# ltk-hall_main_vh.net
KiCad netlist of a schematic drawn in Altium Designer
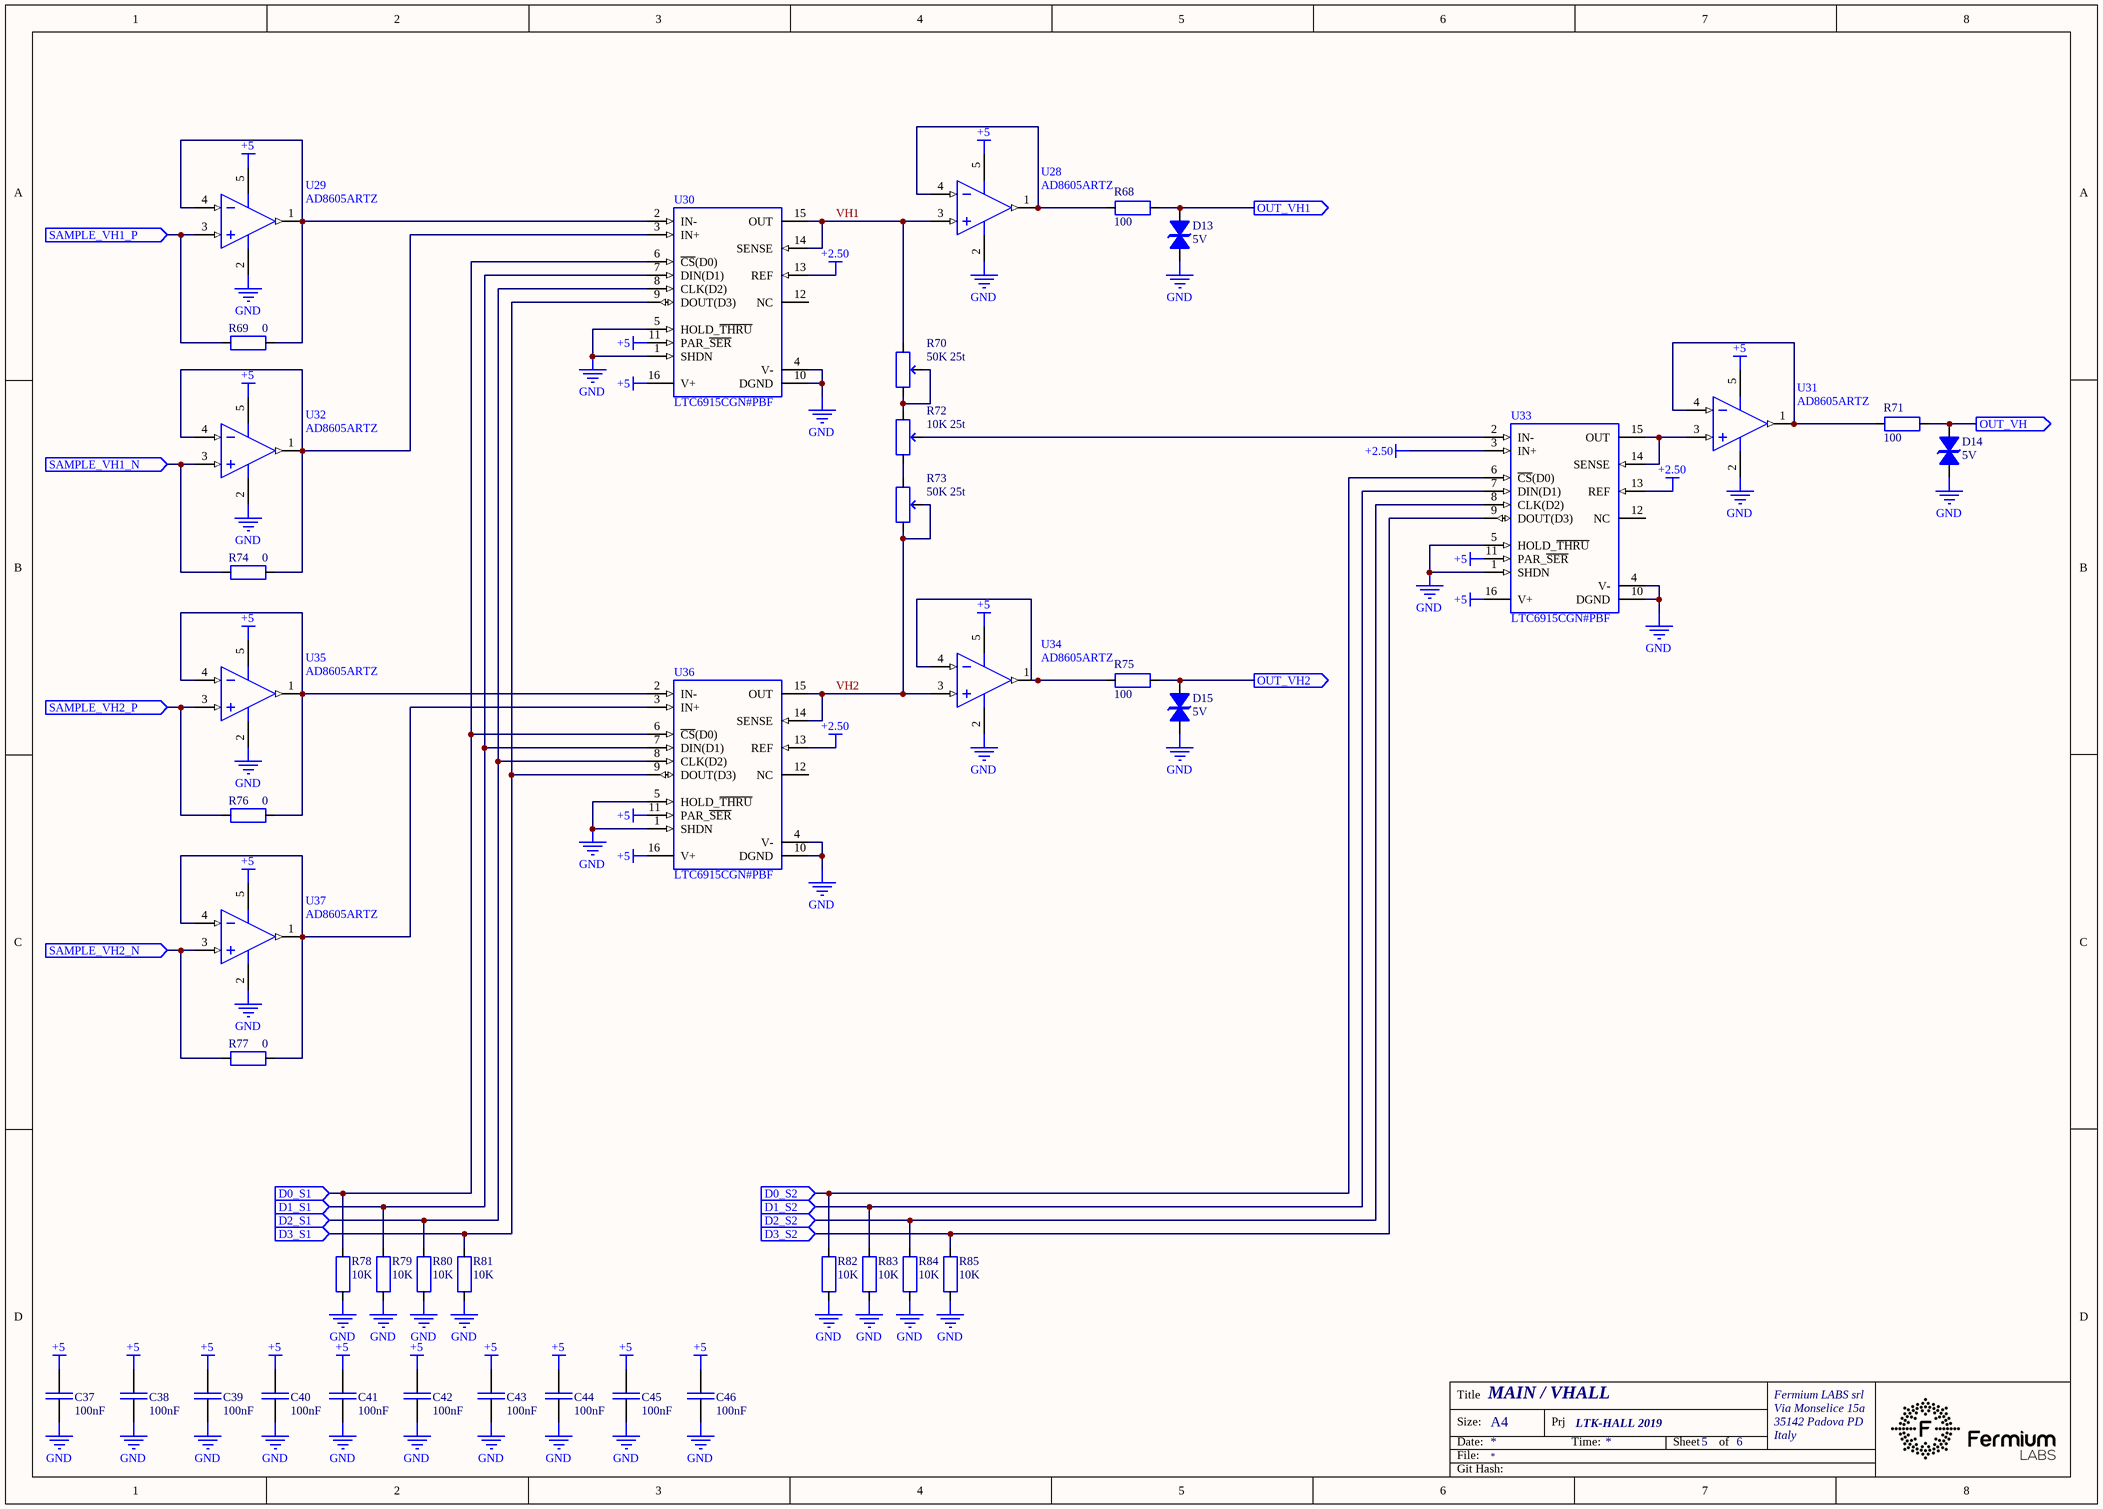
[diagram p0: ltk-hall_main_vh.SchDoc]

(export (version "E")
  (design (tool "Eeschema 10.0.6"))
  (components
    (comp (ref "C37")
      (value "100nF")
      (footprint "CAP 0603_1608")
      (description "CAP SMD MLCC 100nF 25V 0603 X7R")
      (fields (field (name "PART NUMBER") "02841f84-ac15-41b5-9e17-915f8f067828"))
      (libsource (lib "frmdblib") (part "GENERIC_C"))
    )
    (comp (ref "C38")
      (value "100nF")
      (footprint "CAP 0603_1608")
      (description "CAP SMD MLCC 100nF 25V 0603 X7R")
      (fields (field (name "PART NUMBER") "02841f84-ac15-41b5-9e17-915f8f067828"))
      (libsource (lib "frmdblib") (part "GENERIC_C"))
    )
    (comp (ref "C39")
      (value "100nF")
      (footprint "CAP 0603_1608")
      (description "CAP SMD MLCC 100nF 25V 0603 X7R")
      (fields (field (name "PART NUMBER") "02841f84-ac15-41b5-9e17-915f8f067828"))
      (libsource (lib "frmdblib") (part "GENERIC_C"))
    )
    (comp (ref "C40")
      (value "100nF")
      (footprint "CAP 0603_1608")
      (description "CAP SMD MLCC 100nF 25V 0603 X7R")
      (fields (field (name "PART NUMBER") "02841f84-ac15-41b5-9e17-915f8f067828"))
      (libsource (lib "frmdblib") (part "GENERIC_C"))
    )
    (comp (ref "C41")
      (value "100nF")
      (footprint "CAP 0603_1608")
      (description "CAP SMD MLCC 100nF 25V 0603 X7R")
      (fields (field (name "PART NUMBER") "02841f84-ac15-41b5-9e17-915f8f067828"))
      (libsource (lib "frmdblib") (part "GENERIC_C"))
    )
    (comp (ref "C42")
      (value "100nF")
      (footprint "CAP 0603_1608")
      (description "CAP SMD MLCC 100nF 25V 0603 X7R")
      (fields (field (name "PART NUMBER") "02841f84-ac15-41b5-9e17-915f8f067828"))
      (libsource (lib "frmdblib") (part "GENERIC_C"))
    )
    (comp (ref "C43")
      (value "100nF")
      (footprint "CAP 0603_1608")
      (description "CAP SMD MLCC 100nF 25V 0603 X7R")
      (fields (field (name "PART NUMBER") "02841f84-ac15-41b5-9e17-915f8f067828"))
      (libsource (lib "frmdblib") (part "GENERIC_C"))
    )
    (comp (ref "C44")
      (value "100nF")
      (footprint "CAP 0603_1608")
      (description "CAP SMD MLCC 100nF 25V 0603 X7R")
      (fields (field (name "PART NUMBER") "02841f84-ac15-41b5-9e17-915f8f067828"))
      (libsource (lib "frmdblib") (part "GENERIC_C"))
    )
    (comp (ref "C45")
      (value "100nF")
      (footprint "CAP 0603_1608")
      (description "CAP SMD MLCC 100nF 25V 0603 X7R")
      (fields (field (name "PART NUMBER") "02841f84-ac15-41b5-9e17-915f8f067828"))
      (libsource (lib "frmdblib") (part "GENERIC_C"))
    )
    (comp (ref "C46")
      (value "100nF")
      (footprint "CAP 0603_1608")
      (description "CAP SMD MLCC 100nF 25V 0603 X7R")
      (fields (field (name "PART NUMBER") "02841f84-ac15-41b5-9e17-915f8f067828"))
      (libsource (lib "frmdblib") (part "GENERIC_C"))
    )
    (comp (ref "D13")
      (value "5V")
      (footprint "SOD523F")
      (description "DIODE SMD TVS 5V BIDIRECTIONAL SOD-523")
      (fields (field (name "PART NUMBER") "daa58212-38e2-4326-a156-8e48058c46f1"))
      (libsource (lib "frmdblib") (part "GENERIC_D_TVS_BI"))
    )
    (comp (ref "D14")
      (value "5V")
      (footprint "SOD523F")
      (description "DIODE SMD TVS 5V BIDIRECTIONAL SOD-523")
      (fields (field (name "PART NUMBER") "daa58212-38e2-4326-a156-8e48058c46f1"))
      (libsource (lib "frmdblib") (part "GENERIC_D_TVS_BI"))
    )
    (comp (ref "D15")
      (value "5V")
      (footprint "SOD523F")
      (description "DIODE SMD TVS 5V BIDIRECTIONAL SOD-523")
      (fields (field (name "PART NUMBER") "daa58212-38e2-4326-a156-8e48058c46f1"))
      (libsource (lib "frmdblib") (part "GENERIC_D_TVS_BI"))
    )
    (comp (ref "R68")
      (value "100")
      (footprint "RES 0603_1608")
      (description "RES SMD 100 OHM 1% 1/10W 0603")
      (fields (field (name "PART NUMBER") "0a6c4b74-f837-4563-b154-6e196d753525"))
      (libsource (lib "frmdblib") (part "GENERIC_R"))
    )
    (comp (ref "R69")
      (value "0")
      (footprint "RES 0603_1608")
      (description "RES SMD 0 OHM 5% 1/10W 0603")
      (fields (field (name "PART NUMBER") "6ae227f9-847f-4766-8522-e11a83531204"))
      (libsource (lib "frmdblib") (part "GENERIC_R"))
    )
    (comp (ref "R70")
      (value "50K 25t")
      (footprint "F9540903-09ED-4909-856A-DED10E64451E")
      (description "POT TRIMMER LINEAR 50K 25TURNS VERT THT")
      (fields (field (name "PART NUMBER") "90164141-8820-4471-9a6f-9a984ce9068c"))
      (libsource (lib "frmdblib") (part "GENERIC_R_VAR"))
    )
    (comp (ref "R71")
      (value "100")
      (footprint "RES 0603_1608")
      (description "RES SMD 100 OHM 1% 1/10W 0603")
      (fields (field (name "PART NUMBER") "0a6c4b74-f837-4563-b154-6e196d753525"))
      (libsource (lib "frmdblib") (part "GENERIC_R"))
    )
    (comp (ref "R72")
      (value "10K 25t")
      (footprint "F9540903-09ED-4909-856A-DED10E64451E")
      (description "POT TRIMMER LINEAR 10K 25TURNS VERT THT")
      (fields (field (name "PART NUMBER") "613f65ed-4d8d-44d0-9fe5-67eff78392c9"))
      (libsource (lib "frmdblib") (part "GENERIC_R_VAR"))
    )
    (comp (ref "R73")
      (value "50K 25t")
      (footprint "F9540903-09ED-4909-856A-DED10E64451E")
      (description "POT TRIMMER LINEAR 50K 25TURNS VERT THT")
      (fields (field (name "PART NUMBER") "90164141-8820-4471-9a6f-9a984ce9068c"))
      (libsource (lib "frmdblib") (part "GENERIC_R_VAR"))
    )
    (comp (ref "R74")
      (value "0")
      (footprint "RES 0603_1608")
      (description "RES SMD 0 OHM 5% 1/10W 0603")
      (fields (field (name "PART NUMBER") "6ae227f9-847f-4766-8522-e11a83531204"))
      (libsource (lib "frmdblib") (part "GENERIC_R"))
    )
    (comp (ref "R75")
      (value "100")
      (footprint "RES 0603_1608")
      (description "RES SMD 100 OHM 1% 1/10W 0603")
      (fields (field (name "PART NUMBER") "0a6c4b74-f837-4563-b154-6e196d753525"))
      (libsource (lib "frmdblib") (part "GENERIC_R"))
    )
    (comp (ref "R76")
      (value "0")
      (footprint "RES 0603_1608")
      (description "RES SMD 0 OHM 5% 1/10W 0603")
      (fields (field (name "PART NUMBER") "6ae227f9-847f-4766-8522-e11a83531204"))
      (libsource (lib "frmdblib") (part "GENERIC_R"))
    )
    (comp (ref "R77")
      (value "0")
      (footprint "RES 0603_1608")
      (description "RES SMD 0 OHM 5% 1/10W 0603")
      (fields (field (name "PART NUMBER") "6ae227f9-847f-4766-8522-e11a83531204"))
      (libsource (lib "frmdblib") (part "GENERIC_R"))
    )
    (comp (ref "R78")
      (value "10K")
      (footprint "RES 0603_1608")
      (description "RES SMD 10K OHM 1% 1/10W 0603")
      (fields (field (name "PART NUMBER") "93242766-ba1d-462d-b58f-ce1dfc4129c8"))
      (libsource (lib "frmdblib") (part "GENERIC_R"))
    )
    (comp (ref "R79")
      (value "10K")
      (footprint "RES 0603_1608")
      (description "RES SMD 10K OHM 1% 1/10W 0603")
      (fields (field (name "PART NUMBER") "93242766-ba1d-462d-b58f-ce1dfc4129c8"))
      (libsource (lib "frmdblib") (part "GENERIC_R"))
    )
    (comp (ref "R80")
      (value "10K")
      (footprint "RES 0603_1608")
      (description "RES SMD 10K OHM 1% 1/10W 0603")
      (fields (field (name "PART NUMBER") "93242766-ba1d-462d-b58f-ce1dfc4129c8"))
      (libsource (lib "frmdblib") (part "GENERIC_R"))
    )
    (comp (ref "R81")
      (value "10K")
      (footprint "RES 0603_1608")
      (description "RES SMD 10K OHM 1% 1/10W 0603")
      (fields (field (name "PART NUMBER") "93242766-ba1d-462d-b58f-ce1dfc4129c8"))
      (libsource (lib "frmdblib") (part "GENERIC_R"))
    )
    (comp (ref "R82")
      (value "10K")
      (footprint "RES 0603_1608")
      (description "RES SMD 10K OHM 1% 1/10W 0603")
      (fields (field (name "PART NUMBER") "93242766-ba1d-462d-b58f-ce1dfc4129c8"))
      (libsource (lib "frmdblib") (part "GENERIC_R"))
    )
    (comp (ref "R83")
      (value "10K")
      (footprint "RES 0603_1608")
      (description "RES SMD 10K OHM 1% 1/10W 0603")
      (fields (field (name "PART NUMBER") "93242766-ba1d-462d-b58f-ce1dfc4129c8"))
      (libsource (lib "frmdblib") (part "GENERIC_R"))
    )
    (comp (ref "R84")
      (value "10K")
      (footprint "RES 0603_1608")
      (description "RES SMD 10K OHM 1% 1/10W 0603")
      (fields (field (name "PART NUMBER") "93242766-ba1d-462d-b58f-ce1dfc4129c8"))
      (libsource (lib "frmdblib") (part "GENERIC_R"))
    )
    (comp (ref "R85")
      (value "10K")
      (footprint "RES 0603_1608")
      (description "RES SMD 10K OHM 1% 1/10W 0603")
      (fields (field (name "PART NUMBER") "93242766-ba1d-462d-b58f-ce1dfc4129c8"))
      (libsource (lib "frmdblib") (part "GENERIC_R"))
    )
    (comp (ref "U28")
      (value "AD8605ARTZ")
      (footprint "A3DDA0BC-073E-4B18-9613-F713A7EC1E27")
      (description "IC OPAMP 65uV 1pA RRIO 5V 80mA SOT-23-5")
      (fields (field (name "PART NUMBER") "5610e9ea-bca8-49b2-8e5f-11409231f6a4"))
      (libsource (lib "frmdblib") (part "8096D751-9DCE-401B-B65E-AAEE0733EA70"))
    )
    (comp (ref "U29")
      (value "AD8605ARTZ")
      (footprint "A3DDA0BC-073E-4B18-9613-F713A7EC1E27")
      (description "IC OPAMP 65uV 1pA RRIO 5V 80mA SOT-23-5")
      (fields (field (name "PART NUMBER") "5610e9ea-bca8-49b2-8e5f-11409231f6a4"))
      (libsource (lib "frmdblib") (part "8096D751-9DCE-401B-B65E-AAEE0733EA70"))
    )
    (comp (ref "U30")
      (value "LTC6915CGN#PBF")
      (footprint "517EE8A2-9FD8-4174-996D-BDBF76CA3EEB")
      (description "IC PGA G0-4094 SPI-PARALLEL 5V RRIO SSOP-16")
      (fields (field (name "PART NUMBER") "59fe82cd-fd18-4813-9f52-e2e78a460aff"))
      (libsource (lib "frmdblib") (part "092C41BF-C4B2-4D13-B4E9-531E546592A0"))
    )
    (comp (ref "U31")
      (value "AD8605ARTZ")
      (footprint "A3DDA0BC-073E-4B18-9613-F713A7EC1E27")
      (description "IC OPAMP 65uV 1pA RRIO 5V 80mA SOT-23-5")
      (fields (field (name "PART NUMBER") "5610e9ea-bca8-49b2-8e5f-11409231f6a4"))
      (libsource (lib "frmdblib") (part "8096D751-9DCE-401B-B65E-AAEE0733EA70"))
    )
    (comp (ref "U32")
      (value "AD8605ARTZ")
      (footprint "A3DDA0BC-073E-4B18-9613-F713A7EC1E27")
      (description "IC OPAMP 65uV 1pA RRIO 5V 80mA SOT-23-5")
      (fields (field (name "PART NUMBER") "5610e9ea-bca8-49b2-8e5f-11409231f6a4"))
      (libsource (lib "frmdblib") (part "8096D751-9DCE-401B-B65E-AAEE0733EA70"))
    )
    (comp (ref "U33")
      (value "LTC6915CGN#PBF")
      (footprint "517EE8A2-9FD8-4174-996D-BDBF76CA3EEB")
      (description "IC PGA G0-4094 SPI-PARALLEL 5V RRIO SSOP-16")
      (fields (field (name "PART NUMBER") "59fe82cd-fd18-4813-9f52-e2e78a460aff"))
      (libsource (lib "frmdblib") (part "092C41BF-C4B2-4D13-B4E9-531E546592A0"))
    )
    (comp (ref "U34")
      (value "AD8605ARTZ")
      (footprint "A3DDA0BC-073E-4B18-9613-F713A7EC1E27")
      (description "IC OPAMP 65uV 1pA RRIO 5V 80mA SOT-23-5")
      (fields (field (name "PART NUMBER") "5610e9ea-bca8-49b2-8e5f-11409231f6a4"))
      (libsource (lib "frmdblib") (part "8096D751-9DCE-401B-B65E-AAEE0733EA70"))
    )
    (comp (ref "U35")
      (value "AD8605ARTZ")
      (footprint "A3DDA0BC-073E-4B18-9613-F713A7EC1E27")
      (description "IC OPAMP 65uV 1pA RRIO 5V 80mA SOT-23-5")
      (fields (field (name "PART NUMBER") "5610e9ea-bca8-49b2-8e5f-11409231f6a4"))
      (libsource (lib "frmdblib") (part "8096D751-9DCE-401B-B65E-AAEE0733EA70"))
    )
    (comp (ref "U36")
      (value "LTC6915CGN#PBF")
      (footprint "517EE8A2-9FD8-4174-996D-BDBF76CA3EEB")
      (description "IC PGA G0-4094 SPI-PARALLEL 5V RRIO SSOP-16")
      (fields (field (name "PART NUMBER") "59fe82cd-fd18-4813-9f52-e2e78a460aff"))
      (libsource (lib "frmdblib") (part "092C41BF-C4B2-4D13-B4E9-531E546592A0"))
    )
    (comp (ref "U37")
      (value "AD8605ARTZ")
      (footprint "A3DDA0BC-073E-4B18-9613-F713A7EC1E27")
      (description "IC OPAMP 65uV 1pA RRIO 5V 80mA SOT-23-5")
      (fields (field (name "PART NUMBER") "5610e9ea-bca8-49b2-8e5f-11409231f6a4"))
      (libsource (lib "frmdblib") (part "8096D751-9DCE-401B-B65E-AAEE0733EA70"))
    )
  )
  (nets
    (net (code "1") (name "+2.50") (class "Default")
      (node (ref "U30") (pin "13") (pinfunction "REF_13") (pintype "input"))
      (node (ref "U33") (pin "13") (pinfunction "REF_13") (pintype "input"))
      (node (ref "U33") (pin "3") (pinfunction "IN+_3") (pintype "input"))
      (node (ref "U36") (pin "13") (pinfunction "REF_13") (pintype "input"))
    )
    (net (code "2") (name "+5") (class "Default")
      (node (ref "C37") (pin "1") (pintype "passive"))
      (node (ref "C38") (pin "1") (pintype "passive"))
      (node (ref "C39") (pin "1") (pintype "passive"))
      (node (ref "C40") (pin "1") (pintype "passive"))
      (node (ref "C41") (pin "1") (pintype "passive"))
      (node (ref "C42") (pin "1") (pintype "passive"))
      (node (ref "C43") (pin "1") (pintype "passive"))
      (node (ref "C44") (pin "1") (pintype "passive"))
      (node (ref "C45") (pin "1") (pintype "passive"))
      (node (ref "C46") (pin "1") (pintype "passive"))
      (node (ref "U28") (pin "5") (pinfunction "+V_5") (pintype "power_in"))
      (node (ref "U29") (pin "5") (pinfunction "+V_5") (pintype "power_in"))
      (node (ref "U30") (pin "11") (pinfunction "PAR_~{SER}_11") (pintype "input"))
      (node (ref "U30") (pin "16") (pinfunction "V+_16") (pintype "power_in"))
      (node (ref "U31") (pin "5") (pinfunction "+V_5") (pintype "power_in"))
      (node (ref "U32") (pin "5") (pinfunction "+V_5") (pintype "power_in"))
      (node (ref "U33") (pin "11") (pinfunction "PAR_~{SER}_11") (pintype "input"))
      (node (ref "U33") (pin "16") (pinfunction "V+_16") (pintype "power_in"))
      (node (ref "U34") (pin "5") (pinfunction "+V_5") (pintype "power_in"))
      (node (ref "U35") (pin "5") (pinfunction "+V_5") (pintype "power_in"))
      (node (ref "U36") (pin "11") (pinfunction "PAR_~{SER}_11") (pintype "input"))
      (node (ref "U36") (pin "16") (pinfunction "V+_16") (pintype "power_in"))
      (node (ref "U37") (pin "5") (pinfunction "+V_5") (pintype "power_in"))
    )
    (net (code "3") (name "/D0_S1") (class "Default")
      (node (ref "R78") (pin "2") (pintype "passive"))
      (node (ref "U30") (pin "6") (pinfunction "~{CS}(D0)_6") (pintype "input"))
      (node (ref "U36") (pin "6") (pinfunction "~{CS}(D0)_6") (pintype "input"))
    )
    (net (code "4") (name "/D0_S2") (class "Default")
      (node (ref "R82") (pin "2") (pintype "passive"))
      (node (ref "U33") (pin "6") (pinfunction "~{CS}(D0)_6") (pintype "input"))
    )
    (net (code "5") (name "/D1_S1") (class "Default")
      (node (ref "R79") (pin "2") (pintype "passive"))
      (node (ref "U30") (pin "7") (pinfunction "DIN(D1)_7") (pintype "input"))
      (node (ref "U36") (pin "7") (pinfunction "DIN(D1)_7") (pintype "input"))
    )
    (net (code "6") (name "/D1_S2") (class "Default")
      (node (ref "R83") (pin "2") (pintype "passive"))
      (node (ref "U33") (pin "7") (pinfunction "DIN(D1)_7") (pintype "input"))
    )
    (net (code "7") (name "/D2_S1") (class "Default")
      (node (ref "R80") (pin "2") (pintype "passive"))
      (node (ref "U30") (pin "8") (pinfunction "CLK(D2)_8") (pintype "input"))
      (node (ref "U36") (pin "8") (pinfunction "CLK(D2)_8") (pintype "input"))
    )
    (net (code "8") (name "/D2_S2") (class "Default")
      (node (ref "R84") (pin "2") (pintype "passive"))
      (node (ref "U33") (pin "8") (pinfunction "CLK(D2)_8") (pintype "input"))
    )
    (net (code "9") (name "/D3_S1") (class "Default")
      (node (ref "R81") (pin "2") (pintype "passive"))
      (node (ref "U30") (pin "9") (pinfunction "DOUT(D3)_9") (pintype "bidirectional"))
      (node (ref "U36") (pin "9") (pinfunction "DOUT(D3)_9") (pintype "bidirectional"))
    )
    (net (code "10") (name "/D3_S2") (class "Default")
      (node (ref "R85") (pin "2") (pintype "passive"))
      (node (ref "U33") (pin "9") (pinfunction "DOUT(D3)_9") (pintype "bidirectional"))
    )
    (net (code "11") (name "/OUT_VH") (class "Default")
      (node (ref "D14") (pin "1") (pintype "passive"))
      (node (ref "R71") (pin "2") (pintype "passive"))
    )
    (net (code "12") (name "/OUT_VH1") (class "Default")
      (node (ref "D13") (pin "1") (pintype "passive"))
      (node (ref "R68") (pin "2") (pintype "passive"))
    )
    (net (code "13") (name "/OUT_VH2") (class "Default")
      (node (ref "D15") (pin "1") (pintype "passive"))
      (node (ref "R75") (pin "2") (pintype "passive"))
    )
    (net (code "14") (name "/SAMPLE_VH1_N") (class "Default")
      (node (ref "R74") (pin "1") (pintype "passive"))
      (node (ref "U32") (pin "3") (pinfunction "+IN_3") (pintype "input"))
    )
    (net (code "15") (name "/SAMPLE_VH1_P") (class "Default")
      (node (ref "R69") (pin "1") (pintype "passive"))
      (node (ref "U29") (pin "3") (pinfunction "+IN_3") (pintype "input"))
    )
    (net (code "16") (name "/SAMPLE_VH2_N") (class "Default")
      (node (ref "R77") (pin "1") (pintype "passive"))
      (node (ref "U37") (pin "3") (pinfunction "+IN_3") (pintype "input"))
    )
    (net (code "17") (name "/SAMPLE_VH2_P") (class "Default")
      (node (ref "R76") (pin "1") (pintype "passive"))
      (node (ref "U35") (pin "3") (pinfunction "+IN_3") (pintype "input"))
    )
    (net (code "18") (name "/VH1") (class "Default")
      (node (ref "R70") (pin "1") (pintype "passive"))
      (node (ref "U28") (pin "3") (pinfunction "+IN_3") (pintype "input"))
      (node (ref "U30") (pin "14") (pinfunction "SENSE_14") (pintype "input"))
      (node (ref "U30") (pin "15") (pinfunction "OUT_15") (pintype "tri_state"))
    )
    (net (code "19") (name "/VH2") (class "Default")
      (node (ref "R73") (pin "2") (pintype "passive"))
      (node (ref "R73") (pin "3") (pintype "passive"))
      (node (ref "U34") (pin "3") (pinfunction "+IN_3") (pintype "input"))
      (node (ref "U36") (pin "14") (pinfunction "SENSE_14") (pintype "input"))
      (node (ref "U36") (pin "15") (pinfunction "OUT_15") (pintype "tri_state"))
    )
    (net (code "20") (name "GND") (class "Default")
      (node (ref "C37") (pin "2") (pintype "passive"))
      (node (ref "C38") (pin "2") (pintype "passive"))
      (node (ref "C39") (pin "2") (pintype "passive"))
      (node (ref "C40") (pin "2") (pintype "passive"))
      (node (ref "C41") (pin "2") (pintype "passive"))
      (node (ref "C42") (pin "2") (pintype "passive"))
      (node (ref "C43") (pin "2") (pintype "passive"))
      (node (ref "C44") (pin "2") (pintype "passive"))
      (node (ref "C45") (pin "2") (pintype "passive"))
      (node (ref "C46") (pin "2") (pintype "passive"))
      (node (ref "D13") (pin "2") (pintype "passive"))
      (node (ref "D14") (pin "2") (pintype "passive"))
      (node (ref "D15") (pin "2") (pintype "passive"))
      (node (ref "R78") (pin "1") (pintype "passive"))
      (node (ref "R79") (pin "1") (pintype "passive"))
      (node (ref "R80") (pin "1") (pintype "passive"))
      (node (ref "R81") (pin "1") (pintype "passive"))
      (node (ref "R82") (pin "1") (pintype "passive"))
      (node (ref "R83") (pin "1") (pintype "passive"))
      (node (ref "R84") (pin "1") (pintype "passive"))
      (node (ref "R85") (pin "1") (pintype "passive"))
      (node (ref "U28") (pin "2") (pinfunction "-V_2") (pintype "power_in"))
      (node (ref "U29") (pin "2") (pinfunction "-V_2") (pintype "power_in"))
      (node (ref "U30") (pin "1") (pinfunction "SHDN_1") (pintype "input"))
      (node (ref "U30") (pin "10") (pinfunction "DGND_10") (pintype "power_in"))
      (node (ref "U30") (pin "4") (pinfunction "V-_4") (pintype "power_in"))
      (node (ref "U30") (pin "5") (pinfunction "HOLD_~{THRU}_5") (pintype "input"))
      (node (ref "U31") (pin "2") (pinfunction "-V_2") (pintype "power_in"))
      (node (ref "U32") (pin "2") (pinfunction "-V_2") (pintype "power_in"))
      (node (ref "U33") (pin "1") (pinfunction "SHDN_1") (pintype "input"))
      (node (ref "U33") (pin "10") (pinfunction "DGND_10") (pintype "power_in"))
      (node (ref "U33") (pin "4") (pinfunction "V-_4") (pintype "power_in"))
      (node (ref "U33") (pin "5") (pinfunction "HOLD_~{THRU}_5") (pintype "input"))
      (node (ref "U34") (pin "2") (pinfunction "-V_2") (pintype "power_in"))
      (node (ref "U35") (pin "2") (pinfunction "-V_2") (pintype "power_in"))
      (node (ref "U36") (pin "1") (pinfunction "SHDN_1") (pintype "input"))
      (node (ref "U36") (pin "10") (pinfunction "DGND_10") (pintype "power_in"))
      (node (ref "U36") (pin "4") (pinfunction "V-_4") (pintype "power_in"))
      (node (ref "U36") (pin "5") (pinfunction "HOLD_~{THRU}_5") (pintype "input"))
      (node (ref "U37") (pin "2") (pinfunction "-V_2") (pintype "power_in"))
    )
    (net (code "21") (name "Net-(R70-Pad2)") (class "Default")
      (node (ref "R70") (pin "2") (pintype "passive"))
      (node (ref "R70") (pin "3") (pintype "passive"))
      (node (ref "R72") (pin "3") (pintype "passive"))
    )
    (net (code "22") (name "Net-(R72-Pad1)") (class "Default")
      (node (ref "R72") (pin "1") (pintype "passive"))
      (node (ref "R73") (pin "1") (pintype "passive"))
    )
    (net (code "23") (name "Net-(U28--IN)") (class "Default")
      (node (ref "R68") (pin "1") (pintype "passive"))
      (node (ref "U28") (pin "1") (pinfunction "OUT_1") (pintype "output"))
      (node (ref "U28") (pin "4") (pinfunction "-IN_4") (pintype "input"))
    )
    (net (code "24") (name "Net-(U29--IN)") (class "Default")
      (node (ref "R69") (pin "2") (pintype "passive"))
      (node (ref "U29") (pin "1") (pinfunction "OUT_1") (pintype "output"))
      (node (ref "U29") (pin "4") (pinfunction "-IN_4") (pintype "input"))
      (node (ref "U30") (pin "2") (pinfunction "IN-_2") (pintype "input"))
    )
    (net (code "25") (name "Net-(U30-IN+)") (class "Default")
      (node (ref "R74") (pin "2") (pintype "passive"))
      (node (ref "U30") (pin "3") (pinfunction "IN+_3") (pintype "input"))
      (node (ref "U32") (pin "1") (pinfunction "OUT_1") (pintype "output"))
      (node (ref "U32") (pin "4") (pinfunction "-IN_4") (pintype "input"))
    )
    (net (code "26") (name "Net-(U31-+IN)") (class "Default")
      (node (ref "U31") (pin "3") (pinfunction "+IN_3") (pintype "input"))
      (node (ref "U33") (pin "14") (pinfunction "SENSE_14") (pintype "input"))
      (node (ref "U33") (pin "15") (pinfunction "OUT_15") (pintype "tri_state"))
    )
    (net (code "27") (name "Net-(U31--IN)") (class "Default")
      (node (ref "R71") (pin "1") (pintype "passive"))
      (node (ref "U31") (pin "1") (pinfunction "OUT_1") (pintype "output"))
      (node (ref "U31") (pin "4") (pinfunction "-IN_4") (pintype "input"))
    )
    (net (code "28") (name "Net-(U33-IN-)") (class "Default")
      (node (ref "R72") (pin "2") (pintype "passive"))
      (node (ref "U33") (pin "2") (pinfunction "IN-_2") (pintype "input"))
    )
    (net (code "29") (name "Net-(U34--IN)") (class "Default")
      (node (ref "R75") (pin "1") (pintype "passive"))
      (node (ref "U34") (pin "1") (pinfunction "OUT_1") (pintype "output"))
      (node (ref "U34") (pin "4") (pinfunction "-IN_4") (pintype "input"))
    )
    (net (code "30") (name "Net-(U35--IN)") (class "Default")
      (node (ref "R76") (pin "2") (pintype "passive"))
      (node (ref "U35") (pin "1") (pinfunction "OUT_1") (pintype "output"))
      (node (ref "U35") (pin "4") (pinfunction "-IN_4") (pintype "input"))
      (node (ref "U36") (pin "2") (pinfunction "IN-_2") (pintype "input"))
    )
    (net (code "31") (name "Net-(U36-IN+)") (class "Default")
      (node (ref "R77") (pin "2") (pintype "passive"))
      (node (ref "U36") (pin "3") (pinfunction "IN+_3") (pintype "input"))
      (node (ref "U37") (pin "1") (pinfunction "OUT_1") (pintype "output"))
      (node (ref "U37") (pin "4") (pinfunction "-IN_4") (pintype "input"))
    )
    (net (code "32") (name "unconnected-(U30-NC-Pad12)") (class "Default")
      (node (ref "U30") (pin "12") (pinfunction "NC_12") (pintype "passive"))
    )
    (net (code "33") (name "unconnected-(U33-NC-Pad12)") (class "Default")
      (node (ref "U33") (pin "12") (pinfunction "NC_12") (pintype "passive"))
    )
    (net (code "34") (name "unconnected-(U36-NC-Pad12)") (class "Default")
      (node (ref "U36") (pin "12") (pinfunction "NC_12") (pintype "passive"))
    )
  )
)
